# avray28.net
KiCad netlist of a schematic drawn in EAGLE
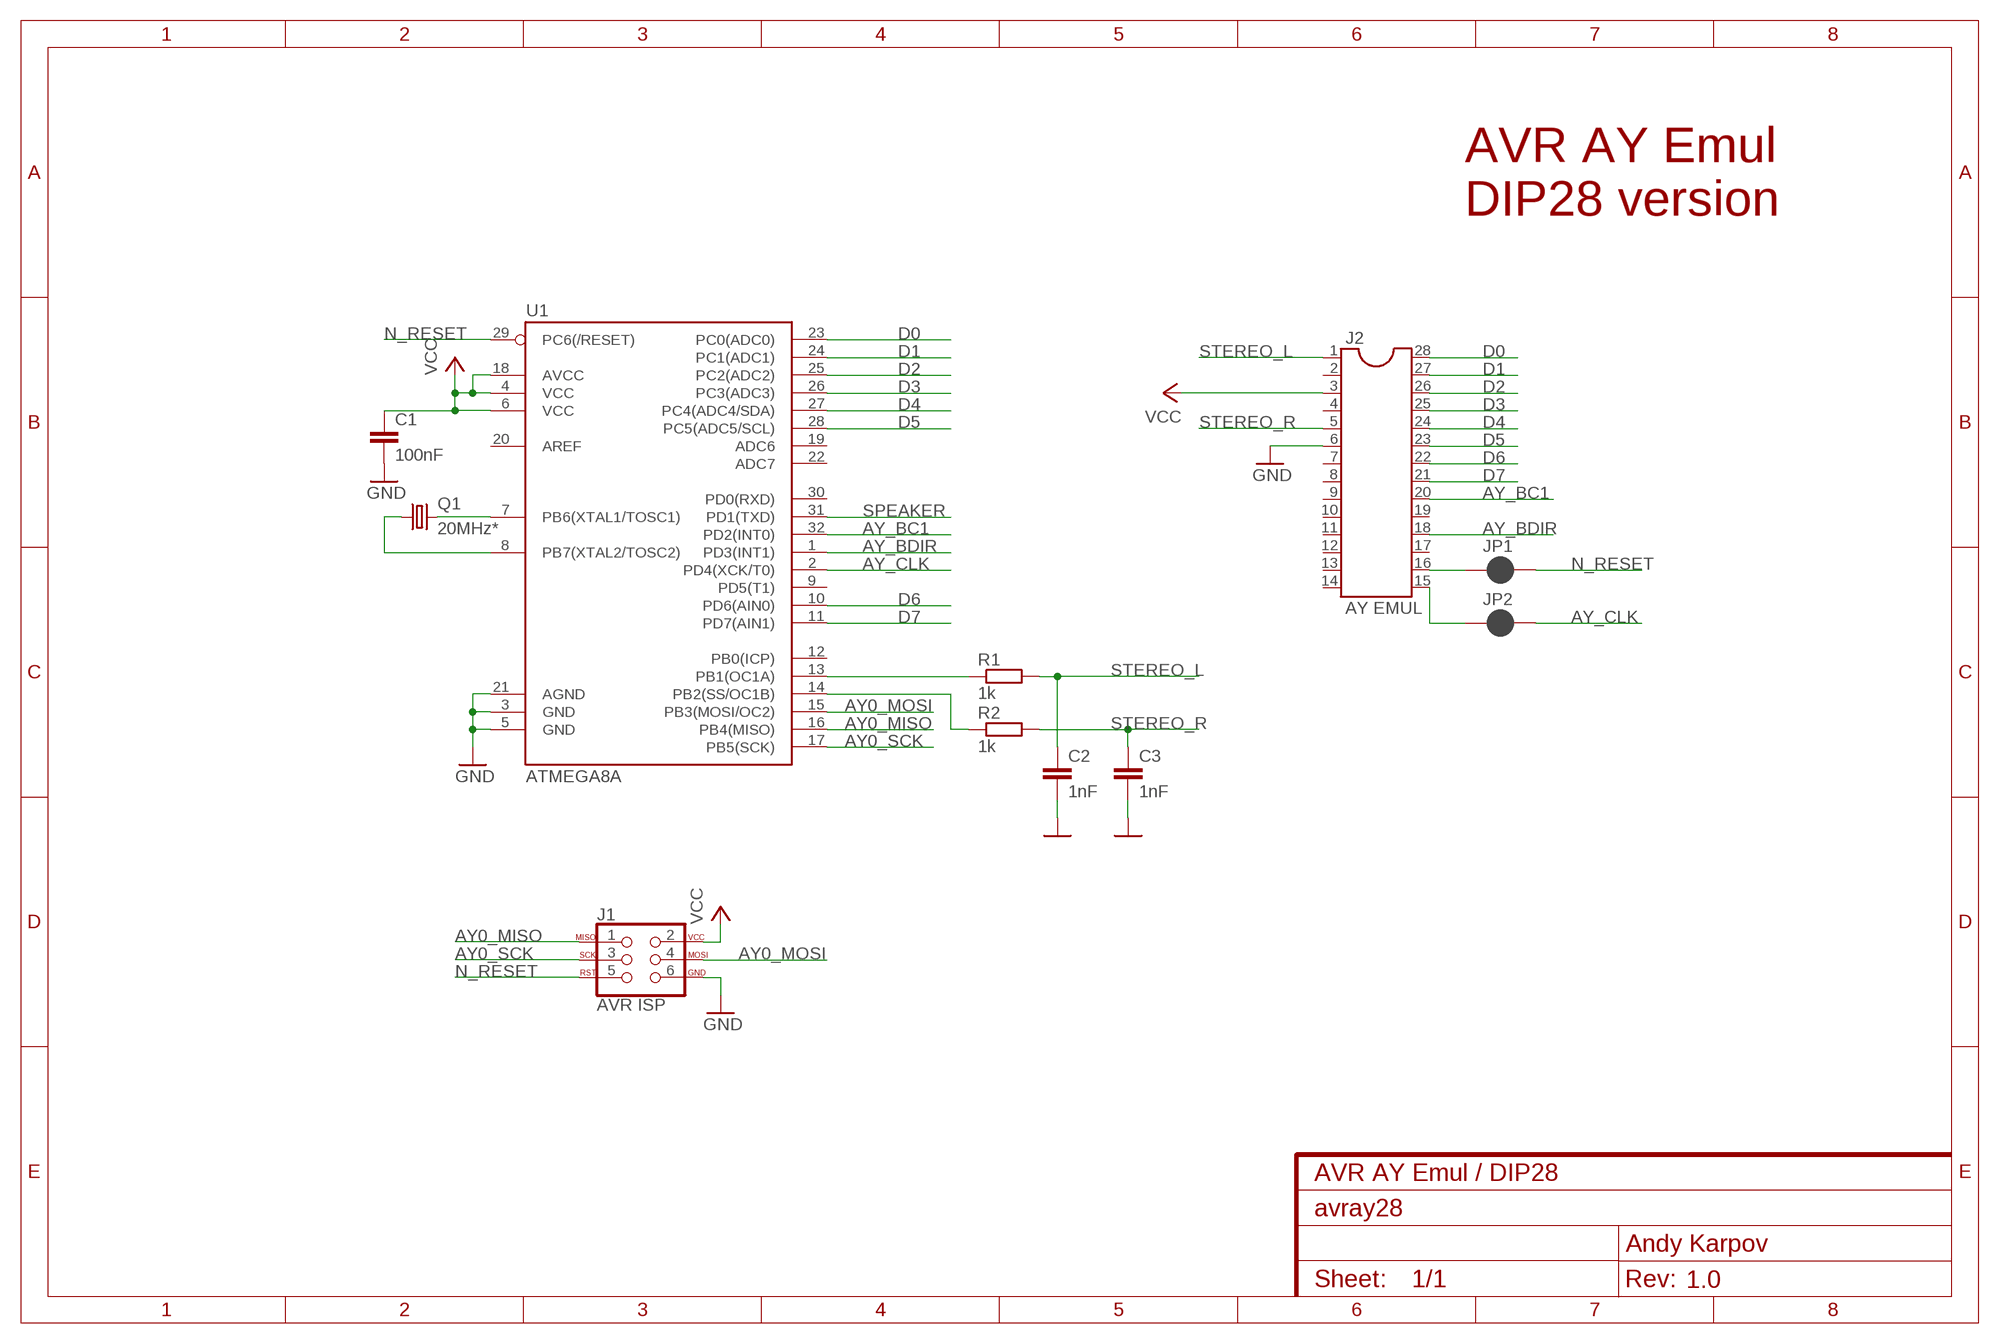
[diagram p0: schematic, sheet 1]

(export (version "E")
  (design (tool "Eeschema 10.0.6"))
  (components
    (comp (ref "C1")
      (value "100nF")
      (footprint "eagle-import:C0805")
      (libsource (lib "eagle-import") (part "C-EUC0805"))
    )
    (comp (ref "C2")
      (value "1nF")
      (footprint "eagle-import:C0805")
      (libsource (lib "eagle-import") (part "C-EUC0805"))
    )
    (comp (ref "C3")
      (value "1nF")
      (footprint "eagle-import:C0805")
      (libsource (lib "eagle-import") (part "C-EUC0805"))
    )
    (comp (ref "J1")
      (value "AVR ISP")
      (footprint "eagle-import:2X3_LOCK")
      (libsource (lib "eagle-import") (part "AVR_SPI_PROG_3X22X3_LOCK"))
    )
    (comp (ref "J2")
      (value "AY EMUL")
      (footprint "eagle-import:DIL28-6")
      (libsource (lib "eagle-import") (part "DIL28"))
    )
    (comp (ref "JP1")
      (value "RST ENA")
      (footprint "eagle-import:SMT-JUMPER_2_NC_PASTE_SILK")
      (libsource (lib "eagle-import") (part "JUMPER-SMT_2_NC_PASTE_SILK"))
    )
    (comp (ref "JP2")
      (value "CLK ENA")
      (footprint "eagle-import:SMT-JUMPER_2_NC_PASTE_SILK")
      (libsource (lib "eagle-import") (part "JUMPER-SMT_2_NC_PASTE_SILK"))
    )
    (comp (ref "Q1")
      (value "20MHz*")
      (footprint "eagle-import:HC49_S")
      (libsource (lib "eagle-import") (part "CRYSTALHC49S"))
    )
    (comp (ref "R1")
      (value "1k")
      (footprint "eagle-import:R0805")
      (libsource (lib "eagle-import") (part "R-EU_R0805"))
    )
    (comp (ref "R2")
      (value "1k")
      (footprint "eagle-import:R0805")
      (libsource (lib "eagle-import") (part "R-EU_R0805"))
    )
    (comp (ref "U1")
      (value "ATMEGA8A")
      (footprint "eagle-import:TQFP32-08")
      (libsource (lib "eagle-import") (part "ATMEGA328P_TQFP"))
    )
  )
  (nets
    (net (code "1") (name "/AY0_MISO") (class "Default")
      (node (ref "J1") (pin "1") (pinfunction "1_1") (pintype "passive"))
      (node (ref "U1") (pin "16") (pinfunction "PB4(MISO)_16") (pintype "bidirectional"))
    )
    (net (code "2") (name "/AY0_MOSI") (class "Default")
      (node (ref "J1") (pin "4") (pinfunction "4_4") (pintype "passive"))
      (node (ref "U1") (pin "15") (pinfunction "PB3(MOSI/OC2)_15") (pintype "bidirectional"))
    )
    (net (code "3") (name "/AY0_SCK") (class "Default")
      (node (ref "J1") (pin "3") (pinfunction "3_3") (pintype "passive"))
      (node (ref "U1") (pin "17") (pinfunction "PB5(SCK)_17") (pintype "bidirectional"))
    )
    (net (code "4") (name "/AY_BC1") (class "Default")
      (node (ref "J2") (pin "20") (pinfunction "20_20") (pintype "passive"))
      (node (ref "U1") (pin "32") (pinfunction "PD2(INT0)_32") (pintype "bidirectional"))
    )
    (net (code "5") (name "/AY_BDIR") (class "Default")
      (node (ref "J2") (pin "18") (pinfunction "18_18") (pintype "passive"))
      (node (ref "U1") (pin "1") (pinfunction "PD3(INT1)_1") (pintype "bidirectional"))
    )
    (net (code "6") (name "/AY_CLK") (class "Default")
      (node (ref "JP2") (pin "2") (pinfunction "2_2") (pintype "passive"))
      (node (ref "U1") (pin "2") (pinfunction "PD4(XCK/T0)_2") (pintype "bidirectional"))
    )
    (net (code "7") (name "/D0") (class "Default")
      (node (ref "J2") (pin "28") (pinfunction "28_28") (pintype "passive"))
      (node (ref "U1") (pin "23") (pinfunction "PC0(ADC0)_23") (pintype "bidirectional"))
    )
    (net (code "8") (name "/D1") (class "Default")
      (node (ref "J2") (pin "27") (pinfunction "27_27") (pintype "passive"))
      (node (ref "U1") (pin "24") (pinfunction "PC1(ADC1)_24") (pintype "bidirectional"))
    )
    (net (code "9") (name "/D2") (class "Default")
      (node (ref "J2") (pin "26") (pinfunction "26_26") (pintype "passive"))
      (node (ref "U1") (pin "25") (pinfunction "PC2(ADC2)_25") (pintype "bidirectional"))
    )
    (net (code "10") (name "/D3") (class "Default")
      (node (ref "J2") (pin "25") (pinfunction "25_25") (pintype "passive"))
      (node (ref "U1") (pin "26") (pinfunction "PC3(ADC3)_26") (pintype "bidirectional"))
    )
    (net (code "11") (name "/D4") (class "Default")
      (node (ref "J2") (pin "24") (pinfunction "24_24") (pintype "passive"))
      (node (ref "U1") (pin "27") (pinfunction "PC4(ADC4/SDA)_27") (pintype "bidirectional"))
    )
    (net (code "12") (name "/D5") (class "Default")
      (node (ref "J2") (pin "23") (pinfunction "23_23") (pintype "passive"))
      (node (ref "U1") (pin "28") (pinfunction "PC5(ADC5/SCL)_28") (pintype "bidirectional"))
    )
    (net (code "13") (name "/D6") (class "Default")
      (node (ref "J2") (pin "22") (pinfunction "22_22") (pintype "passive"))
      (node (ref "U1") (pin "10") (pinfunction "PD6(AIN0)_10") (pintype "bidirectional"))
    )
    (net (code "14") (name "/D7") (class "Default")
      (node (ref "J2") (pin "21") (pinfunction "21_21") (pintype "passive"))
      (node (ref "U1") (pin "11") (pinfunction "PD7(AIN1)_11") (pintype "bidirectional"))
    )
    (net (code "15") (name "/N_RESET") (class "Default")
      (node (ref "J1") (pin "5") (pinfunction "5_5") (pintype "passive"))
      (node (ref "JP1") (pin "2") (pinfunction "2_2") (pintype "passive"))
      (node (ref "U1") (pin "29") (pinfunction "PC6(/RESET)_29") (pintype "bidirectional"))
    )
    (net (code "16") (name "/SPEAKER") (class "Default")
      (node (ref "U1") (pin "31") (pinfunction "PD1(TXD)_31") (pintype "bidirectional"))
    )
    (net (code "17") (name "/STEREO_L") (class "Default")
      (node (ref "C2") (pin "1") (pinfunction "1_1") (pintype "passive"))
      (node (ref "J2") (pin "1") (pinfunction "1_1") (pintype "passive"))
      (node (ref "R1") (pin "2") (pinfunction "2_2") (pintype "passive"))
    )
    (net (code "18") (name "/STEREO_R") (class "Default")
      (node (ref "C3") (pin "1") (pinfunction "1_1") (pintype "passive"))
      (node (ref "J2") (pin "5") (pinfunction "5_5") (pintype "passive"))
      (node (ref "R2") (pin "2") (pinfunction "2_2") (pintype "passive"))
    )
    (net (code "19") (name "GND") (class "Default")
      (node (ref "C1") (pin "2") (pinfunction "2_2") (pintype "passive"))
      (node (ref "C2") (pin "2") (pinfunction "2_2") (pintype "passive"))
      (node (ref "C3") (pin "2") (pinfunction "2_2") (pintype "passive"))
      (node (ref "J1") (pin "6") (pinfunction "6_6") (pintype "passive"))
      (node (ref "J2") (pin "6") (pinfunction "6_6") (pintype "passive"))
      (node (ref "U1") (pin "21") (pinfunction "AGND_21") (pintype "bidirectional"))
      (node (ref "U1") (pin "3") (pinfunction "GND_3") (pintype "bidirectional"))
      (node (ref "U1") (pin "5") (pinfunction "GND_5") (pintype "bidirectional"))
    )
    (net (code "20") (name "Net-(J2-Pad15)") (class "Default")
      (node (ref "J2") (pin "15") (pinfunction "15_15") (pintype "passive"))
      (node (ref "JP2") (pin "1") (pinfunction "1_1") (pintype "passive"))
    )
    (net (code "21") (name "Net-(J2-Pad16)") (class "Default")
      (node (ref "J2") (pin "16") (pinfunction "16_16") (pintype "passive"))
      (node (ref "JP1") (pin "1") (pinfunction "1_1") (pintype "passive"))
    )
    (net (code "22") (name "Net-(U1-PB1(OC1A))") (class "Default")
      (node (ref "R1") (pin "1") (pinfunction "1_1") (pintype "passive"))
      (node (ref "U1") (pin "13") (pinfunction "PB1(OC1A)_13") (pintype "bidirectional"))
    )
    (net (code "23") (name "Net-(U1-PB2(SS{slash}OC1B))") (class "Default")
      (node (ref "R2") (pin "1") (pinfunction "1_1") (pintype "passive"))
      (node (ref "U1") (pin "14") (pinfunction "PB2(SS/OC1B)_14") (pintype "bidirectional"))
    )
    (net (code "24") (name "Net-(U1-PB6(XTAL1{slash}TOSC1))") (class "Default")
      (node (ref "Q1") (pin "2") (pinfunction "2_2") (pintype "passive"))
      (node (ref "U1") (pin "7") (pinfunction "PB6(XTAL1/TOSC1)_7") (pintype "bidirectional"))
    )
    (net (code "25") (name "Net-(U1-PB7(XTAL2{slash}TOSC2))") (class "Default")
      (node (ref "Q1") (pin "1") (pinfunction "1_1") (pintype "passive"))
      (node (ref "U1") (pin "8") (pinfunction "PB7(XTAL2/TOSC2)_8") (pintype "bidirectional"))
    )
    (net (code "26") (name "VCC") (class "Default")
      (node (ref "C1") (pin "1") (pinfunction "1_1") (pintype "passive"))
      (node (ref "J1") (pin "2") (pinfunction "2_2") (pintype "passive"))
      (node (ref "J2") (pin "3") (pinfunction "3_3") (pintype "passive"))
      (node (ref "U1") (pin "18") (pinfunction "AVCC_18") (pintype "bidirectional"))
      (node (ref "U1") (pin "4") (pinfunction "VCC_4") (pintype "bidirectional"))
      (node (ref "U1") (pin "6") (pinfunction "VCC_6") (pintype "bidirectional"))
    )
    (net (code "27") (name "unconnected-(J2-Pad2)") (class "Default")
      (node (ref "J2") (pin "2") (pinfunction "2_2") (pintype "passive"))
    )
    (net (code "28") (name "unconnected-(J2-Pad4)") (class "Default")
      (node (ref "J2") (pin "4") (pinfunction "4_4") (pintype "passive"))
    )
    (net (code "29") (name "unconnected-(J2-Pad7)") (class "Default")
      (node (ref "J2") (pin "7") (pinfunction "7_7") (pintype "passive"))
    )
    (net (code "30") (name "unconnected-(J2-Pad8)") (class "Default")
      (node (ref "J2") (pin "8") (pinfunction "8_8") (pintype "passive"))
    )
    (net (code "31") (name "unconnected-(J2-Pad9)") (class "Default")
      (node (ref "J2") (pin "9") (pinfunction "9_9") (pintype "passive"))
    )
    (net (code "32") (name "unconnected-(J2-Pad10)") (class "Default")
      (node (ref "J2") (pin "10") (pinfunction "10_10") (pintype "passive"))
    )
    (net (code "33") (name "unconnected-(J2-Pad11)") (class "Default")
      (node (ref "J2") (pin "11") (pinfunction "11_11") (pintype "passive"))
    )
    (net (code "34") (name "unconnected-(J2-Pad12)") (class "Default")
      (node (ref "J2") (pin "12") (pinfunction "12_12") (pintype "passive"))
    )
    (net (code "35") (name "unconnected-(J2-Pad13)") (class "Default")
      (node (ref "J2") (pin "13") (pinfunction "13_13") (pintype "passive"))
    )
    (net (code "36") (name "unconnected-(J2-Pad14)") (class "Default")
      (node (ref "J2") (pin "14") (pinfunction "14_14") (pintype "passive"))
    )
    (net (code "37") (name "unconnected-(J2-Pad17)") (class "Default")
      (node (ref "J2") (pin "17") (pinfunction "17_17") (pintype "passive"))
    )
    (net (code "38") (name "unconnected-(J2-Pad19)") (class "Default")
      (node (ref "J2") (pin "19") (pinfunction "19_19") (pintype "passive"))
    )
    (net (code "39") (name "unconnected-(U1-ADC6-Pad19)") (class "Default")
      (node (ref "U1") (pin "19") (pinfunction "ADC6_19") (pintype "bidirectional"))
    )
    (net (code "40") (name "unconnected-(U1-ADC7-Pad22)") (class "Default")
      (node (ref "U1") (pin "22") (pinfunction "ADC7_22") (pintype "bidirectional"))
    )
    (net (code "41") (name "unconnected-(U1-AREF-Pad20)") (class "Default")
      (node (ref "U1") (pin "20") (pinfunction "AREF_20") (pintype "bidirectional"))
    )
    (net (code "42") (name "unconnected-(U1-PB0(ICP)-Pad12)") (class "Default")
      (node (ref "U1") (pin "12") (pinfunction "PB0(ICP)_12") (pintype "bidirectional"))
    )
    (net (code "43") (name "unconnected-(U1-PD0(RXD)-Pad30)") (class "Default")
      (node (ref "U1") (pin "30") (pinfunction "PD0(RXD)_30") (pintype "bidirectional"))
    )
    (net (code "44") (name "unconnected-(U1-PD5(T1)-Pad9)") (class "Default")
      (node (ref "U1") (pin "9") (pinfunction "PD5(T1)_9") (pintype "bidirectional"))
    )
  )
)
